# ST_LINK_V2-1.net
KiCad netlist of a schematic drawn in Altium Designer
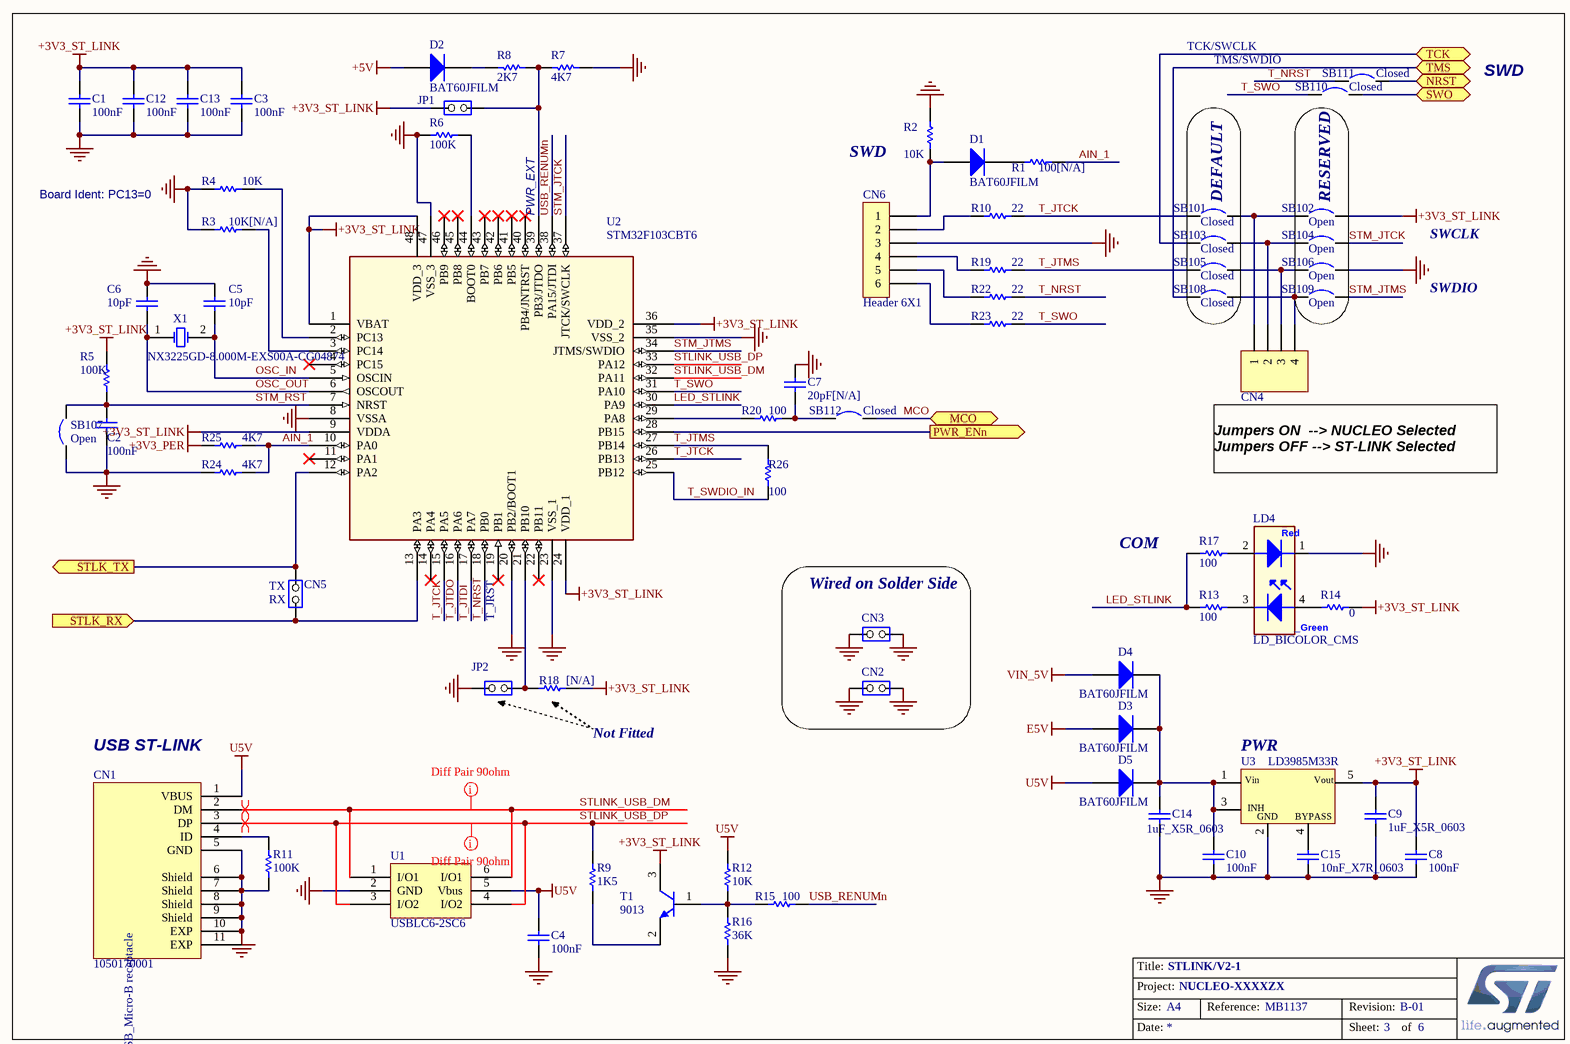
[diagram p0: ST_LINK_V2-1.SCHDOC]

(export (version "E")
  (design (tool "Eeschema 10.0.6"))
  (components
    (comp (ref "C1")
      (value "100nF")
      (footprint "0603C")
      (description "Capacitor 0402 / 0603 / 0805")
      (libsource (lib "MCD_TOOLS") (part "Capacitor_ST"))
    )
    (comp (ref "C2")
      (value "100nF")
      (footprint "0603C")
      (description "Capacitor 0402 / 0603 / 0805")
      (libsource (lib "MCD_TOOLS") (part "Capacitor_ST"))
    )
    (comp (ref "C3")
      (value "100nF")
      (footprint "0603C")
      (description "Capacitor 0402 / 0603 / 0805")
      (libsource (lib "MCD_TOOLS") (part "Capacitor_ST"))
    )
    (comp (ref "C4")
      (value "100nF")
      (footprint "0603C")
      (description "Capacitor 0402 / 0603 / 0805")
      (libsource (lib "MCD_TOOLS") (part "Capacitor_ST"))
    )
    (comp (ref "C5")
      (value "10pF")
      (footprint "0603C")
      (description "Capacitor 0402 / 0603 / 0805")
      (libsource (lib "MCD_TOOLS") (part "Capacitor_ST"))
    )
    (comp (ref "C6")
      (value "10pF")
      (footprint "0603C")
      (description "Capacitor 0402 / 0603 / 0805")
      (libsource (lib "MCD_TOOLS") (part "Capacitor_ST"))
    )
    (comp (ref "C7")
      (value "20pF[N/A]")
      (footprint "0603C")
      (description "Capacitor 0402 / 0603 / 0805")
      (libsource (lib "MCD_TOOLS") (part "Capacitor_ST"))
    )
    (comp (ref "C8")
      (value "100nF")
      (footprint "0603C")
      (description "Capacitor 0402 / 0603 / 0805")
      (libsource (lib "MCD_TOOLS") (part "Capacitor_ST"))
    )
    (comp (ref "C9")
      (value "1uF_X5R_0603")
      (footprint "0603C")
      (description "0603  X5R 1µF")
      (fields (field (name "TOLERANCE") "10%"))
      (libsource (lib "MB963_1") (part "CAP SMD 0603  X5R 1µF 25V 10%"))
    )
    (comp (ref "C10")
      (value "100nF")
      (footprint "0603C")
      (description "Capacitor 0402 / 0603 / 0805")
      (libsource (lib "MCD_TOOLS") (part "Capacitor_ST"))
    )
    (comp (ref "C12")
      (value "100nF")
      (footprint "0603C")
      (description "Capacitor 0402 / 0603 / 0805")
      (libsource (lib "MCD_TOOLS") (part "Capacitor_ST"))
    )
    (comp (ref "C13")
      (value "100nF")
      (footprint "0603C")
      (description "Capacitor 0402 / 0603 / 0805")
      (libsource (lib "MCD_TOOLS") (part "Capacitor_ST"))
    )
    (comp (ref "C14")
      (value "1uF_X5R_0603")
      (footprint "0603C")
      (description "0603  X5R 1µF")
      (fields (field (name "TOLERANCE") "10%"))
      (libsource (lib "MB963_1") (part "CAP SMD 0603  X5R 1µF 25V 10%"))
    )
    (comp (ref "C15")
      (value "10nF_X7R_0603")
      (footprint "0603C")
      (description "0603  X7R 10NF")
      (fields (field (name "TOLERANCE") "10%"))
      (libsource (lib "MB963_1") (part "CAP SMD 0603  X7R 10000PF 50V 10%"))
    )
    (comp (ref "CN1")
      (value "1050170001")
      (footprint "Molex_1050170001")
      (libsource (lib "Smartphone_accessory") (part "1050170001"))
    )
    (comp (ref "CN2") (value "~") (footprint "HDR_1x2_2R54_V_M") (libsource (lib "*") (part "JP2")))
    (comp (ref "CN3") (value "~") (footprint "HDR_1x2_2R54_V_M") (libsource (lib "*") (part "JP2")))
    (comp (ref "CN4")
      (value "Header 4")
      (footprint "HDR_1x4_2R54_V_M")
      (description "Header, 4-Pin, Single row")
      (fields (field (name "PUBLISHER") "Altium Limited"))
      (libsource (lib "Nucleo_64") (part "Header 4"))
    )
    (comp (ref "CN5") (value "~") (footprint "HDR_1x2_2R54_V_M_S") (libsource (lib "MCD_TOOLS") (part "JP2")))
    (comp (ref "CN6")
      (value "Header 6X1")
      (footprint "HDR_1x6_2R54_V_M")
      (description "Header, 6-Pin, Single row")
      (fields (field (name "PUBLISHER") "Altium Limited"))
      (libsource (lib "Nucleo_64") (part "Header 6X1"))
    )
    (comp (ref "D1")
      (value "BAT60JFILM")
      (footprint "SOD-323")
      (libsource (lib "MB1137") (part "BAT60JFILM"))
    )
    (comp (ref "D2")
      (value "BAT60JFILM")
      (footprint "SOD-323")
      (description "Default Diode")
      (fields (field (name "PUBLISHER") "Altium Limited"))
      (libsource (lib "MB1144_1") (part "Diode"))
    )
    (comp (ref "D3")
      (value "BAT60JFILM")
      (footprint "SOD-323")
      (libsource (lib "MB1137") (part "BAT60JFILM"))
    )
    (comp (ref "D4")
      (value "BAT60JFILM")
      (footprint "SOD-323")
      (libsource (lib "MB1137") (part "BAT60JFILM"))
    )
    (comp (ref "D5")
      (value "BAT60JFILM")
      (footprint "SOD-323")
      (libsource (lib "MB1137") (part "BAT60JFILM"))
    )
    (comp (ref "JP1") (value "~") (footprint "HDR_1x2_2R54_V_M_S") (libsource (lib "*") (part "JP2")))
    (comp (ref "JP2") (value "~") (footprint "HDR_1x2_2R54_V_M_S") (libsource (lib "*") (part "JP2")))
    (comp (ref "LD4")
      (value "LD_BICOLOR_CMS")
      (footprint "HSMF-A201")
      (description "Bicolor Led")
      (libsource (lib "MB1137") (part "LD_BICOLOR_CMS"))
    )
    (comp (ref "R1")
      (value "100[N/A]")
      (footprint "0603R")
      (description "Resistor 0402 / 0603 / 0805")
      (libsource (lib "Miscellaneous Devices") (part "Res1"))
    )
    (comp (ref "R2")
      (value "10K")
      (footprint "0603R")
      (description "Resistor 0402 / 0603 / 0805")
      (libsource (lib "Miscellaneous Devices") (part "Res1"))
    )
    (comp (ref "R3")
      (value "10K[N/A]")
      (footprint "0603R")
      (description "Resistor 0402 / 0603 / 0805")
      (libsource (lib "Miscellaneous Devices") (part "Res1"))
    )
    (comp (ref "R4")
      (value "10K")
      (footprint "0603R")
      (description "Resistor 0402 / 0603 / 0805")
      (libsource (lib "Miscellaneous Devices") (part "Res1"))
    )
    (comp (ref "R5")
      (value "100K")
      (footprint "0603R")
      (description "Resistor 0402 / 0603 / 0805")
      (libsource (lib "Miscellaneous Devices") (part "Res1"))
    )
    (comp (ref "R6")
      (value "100K")
      (footprint "0603R")
      (description "Resistor 0402 / 0603 / 0805")
      (libsource (lib "Miscellaneous Devices") (part "Res1"))
    )
    (comp (ref "R7")
      (value "4K7")
      (footprint "0603R")
      (description "Resistor")
      (fields (field (name "PUBLISHER") "Altium Limited"))
      (libsource (lib "") (part "Res1_2"))
    )
    (comp (ref "R8")
      (value "2K7")
      (footprint "0603R")
      (description "Resistor")
      (fields (field (name "PUBLISHER") "Altium Limited"))
      (libsource (lib "") (part "Res1_2"))
    )
    (comp (ref "R9")
      (value "1K5")
      (footprint "0603R")
      (description "Resistor 0402 / 0603 / 0805")
      (libsource (lib "Miscellaneous Devices") (part "Res1"))
    )
    (comp (ref "R10")
      (value "22")
      (footprint "0603R")
      (description "Resistor 0402 / 0603 / 0805")
      (libsource (lib "Miscellaneous Devices") (part "Res1"))
    )
    (comp (ref "R11")
      (value "100K")
      (footprint "0603R")
      (description "Resistor 0402 / 0603 / 0805")
      (libsource (lib "Miscellaneous Devices") (part "Res1"))
    )
    (comp (ref "R12")
      (value "10K")
      (footprint "0603R")
      (description "Resistor")
      (fields (field (name "PUBLISHER") "Altium Limited"))
      (libsource (lib "") (part "Res1_1"))
    )
    (comp (ref "R13")
      (value "100")
      (footprint "0603R")
      (description "Resistor 0402 / 0603 / 0805")
      (libsource (lib "Miscellaneous Devices") (part "Res1"))
    )
    (comp (ref "R14")
      (value "0")
      (footprint "0603R")
      (description "Resistor 0402 / 0603 / 0805")
      (libsource (lib "Miscellaneous Devices") (part "Res1"))
    )
    (comp (ref "R15")
      (value "100")
      (footprint "0603R")
      (description "Resistor 0402 / 0603 / 0805")
      (libsource (lib "Miscellaneous Devices") (part "Res1"))
    )
    (comp (ref "R16")
      (value "36K")
      (footprint "0603R")
      (description "Resistor")
      (fields (field (name "PUBLISHER") "Altium Limited"))
      (libsource (lib "") (part "Res1_1"))
    )
    (comp (ref "R17")
      (value "100")
      (footprint "0603R")
      (description "Resistor 0402 / 0603 / 0805")
      (libsource (lib "Miscellaneous Devices") (part "Res1"))
    )
    (comp (ref "R18")
      (value "[N/A]")
      (footprint "0603R")
      (description "Resistor")
      (fields (field (name "PUBLISHER") "Altium Limited"))
      (libsource (lib "") (part "Res1_1"))
    )
    (comp (ref "R19")
      (value "22")
      (footprint "0603R")
      (description "Resistor 0402 / 0603 / 0805")
      (libsource (lib "Miscellaneous Devices") (part "Res1"))
    )
    (comp (ref "R20")
      (value "100")
      (footprint "0603R")
      (description "Resistor 0402 / 0603 / 0805")
      (libsource (lib "Miscellaneous Devices") (part "Res1"))
    )
    (comp (ref "R22")
      (value "22")
      (footprint "0603R")
      (description "Resistor 0402 / 0603 / 0805")
      (libsource (lib "Miscellaneous Devices") (part "Res1"))
    )
    (comp (ref "R23")
      (value "22")
      (footprint "0603R")
      (description "Resistor 0402 / 0603 / 0805")
      (libsource (lib "Miscellaneous Devices") (part "Res1"))
    )
    (comp (ref "R24")
      (value "4K7")
      (footprint "0603R")
      (description "Resistor 0402 / 0603 / 0805")
      (libsource (lib "Miscellaneous Devices") (part "Res1"))
    )
    (comp (ref "R25")
      (value "4K7")
      (footprint "0603R")
      (description "Resistor 0402 / 0603 / 0805")
      (libsource (lib "Miscellaneous Devices") (part "Res1"))
    )
    (comp (ref "R26")
      (value "100")
      (footprint "0603R")
      (description "Resistor 0402 / 0603 / 0805")
      (libsource (lib "Miscellaneous Devices") (part "Res1"))
    )
    (comp (ref "SB101")
      (value "Closed")
      (footprint "SB_0603")
      (description "Circuit Breaker")
      (fields (field (name "PUBLISHER") "Altium Limited"))
      (libsource (lib "MB1167") (part "Circuit Breaker_close"))
    )
    (comp (ref "SB102")
      (value "Open")
      (footprint "SB_0603")
      (description "Circuit Breaker")
      (fields (field (name "PUBLISHER") "Altium Limited"))
      (libsource (lib "MB1167") (part "Circuit Breaker"))
    )
    (comp (ref "SB103")
      (value "Closed")
      (footprint "SB_0603")
      (description "Circuit Breaker")
      (fields (field (name "PUBLISHER") "Altium Limited"))
      (libsource (lib "MB1167") (part "Circuit Breaker_close"))
    )
    (comp (ref "SB104")
      (value "Open")
      (footprint "SB_0603")
      (description "Circuit Breaker")
      (fields (field (name "PUBLISHER") "Altium Limited"))
      (libsource (lib "MB1167") (part "Circuit Breaker"))
    )
    (comp (ref "SB105")
      (value "Closed")
      (footprint "SB_0603")
      (description "Circuit Breaker")
      (fields (field (name "PUBLISHER") "Altium Limited"))
      (libsource (lib "MB1167") (part "Circuit Breaker_close"))
    )
    (comp (ref "SB106")
      (value "Open")
      (footprint "SB_0603")
      (description "Circuit Breaker")
      (fields (field (name "PUBLISHER") "Altium Limited"))
      (libsource (lib "MB1167") (part "Circuit Breaker"))
    )
    (comp (ref "SB107")
      (value "Open")
      (footprint "SB_0603")
      (description "Circuit Breaker")
      (fields (field (name "PUBLISHER") "Altium Limited"))
      (libsource (lib "MB1167") (part "Circuit Breaker"))
    )
    (comp (ref "SB108")
      (value "Closed")
      (footprint "SB_0603")
      (description "Circuit Breaker")
      (fields (field (name "PUBLISHER") "Altium Limited"))
      (libsource (lib "MB1167") (part "Circuit Breaker_close"))
    )
    (comp (ref "SB109")
      (value "Open")
      (footprint "SB_0603")
      (description "Circuit Breaker")
      (fields (field (name "PUBLISHER") "Altium Limited"))
      (libsource (lib "MB1167") (part "Circuit Breaker"))
    )
    (comp (ref "SB110")
      (value "Closed")
      (footprint "SB_0603")
      (description "Circuit Breaker")
      (fields (field (name "PUBLISHER") "Altium Limited"))
      (libsource (lib "MB1167") (part "Circuit Breaker_close"))
    )
    (comp (ref "SB111")
      (value "Closed")
      (footprint "SB_0603")
      (description "Circuit Breaker")
      (fields (field (name "PUBLISHER") "Altium Limited"))
      (libsource (lib "MB1167") (part "Circuit Breaker_close"))
    )
    (comp (ref "SB112")
      (value "Closed")
      (footprint "SB_0603")
      (description "Circuit Breaker")
      (fields (field (name "PUBLISHER") "Altium Limited"))
      (libsource (lib "MB1167") (part "Circuit Breaker_close"))
    )
    (comp (ref "T1")
      (value "9013")
      (footprint "SOT-23")
      (description "NPN Bipolar Transistor")
      (fields (field (name "PUBLISHER") "Altium Limited"))
      (libsource (lib "MB1167") (part "NPN"))
    )
    (comp (ref "U1")
      (value "USBLC6-2SC6")
      (footprint "SOT23-6L")
      (libsource (lib "MB1137") (part "USBLC6-2SC6"))
    )
    (comp (ref "U2")
      (value "STM32F103CBT6")
      (footprint "LQFP48_0R5_7x7")
      (description "Medium-density performance line ARM-based 32-bit MCU with 64KB Flash")
      (libsource (lib "Nucleo_64") (part "STM32F103CBT6"))
    )
    (comp (ref "U3")
      (value "LD3985M33R")
      (footprint "SOT-23-5L")
      (description "Ultra low drop-low noise BiCMOS voltage, regulators low ESR capacitors compatible")
      (libsource (lib "MCD_TOOLS") (part "LD3985M33R"))
    )
    (comp (ref "X1")
      (value "NX3225GD-8.000M-EXS00A-CG04874")
      (footprint "OSC_2SM_3R2x2R5")
      (description "Crystal Oscillator")
      (fields (field (name "PUBLISHER") "Altium Limited"))
      (libsource (lib "MB963_1") (part "XTAL"))
    )
  )
  (nets
    (net (code "1") (name "+3V3_PER") (class "Default")
      (node (ref "R25") (pin "1") (pinfunction "1_1") (pintype "passive"))
    )
    (net (code "2") (name "+3V3_ST_LINK") (class "Default")
      (node (ref "C1") (pin "2") (pinfunction "2_2") (pintype "passive"))
      (node (ref "C12") (pin "2") (pinfunction "2_2") (pintype "passive"))
      (node (ref "C13") (pin "2") (pinfunction "2_2") (pintype "passive"))
      (node (ref "C3") (pin "2") (pinfunction "2_2") (pintype "passive"))
      (node (ref "C8") (pin "2") (pinfunction "2_2") (pintype "passive"))
      (node (ref "C9") (pin "1") (pinfunction "1_1") (pintype "passive"))
      (node (ref "JP1") (pin "1") (pinfunction "COMMON_1") (pintype "passive"))
      (node (ref "R14") (pin "2") (pinfunction "2_2") (pintype "passive"))
      (node (ref "R18") (pin "1") (pinfunction "1_1") (pintype "passive"))
      (node (ref "R5") (pin "2") (pinfunction "2_2") (pintype "passive"))
      (node (ref "SB102") (pin "2") (pinfunction "2_2") (pintype "passive"))
      (node (ref "T1") (pin "3") (pinfunction "C_3") (pintype "passive"))
      (node (ref "U2") (pin "1") (pinfunction "VBAT_1") (pintype "power_in"))
      (node (ref "U2") (pin "24") (pinfunction "VDD_1_24") (pintype "power_in"))
      (node (ref "U2") (pin "36") (pinfunction "VDD_2_36") (pintype "power_in"))
      (node (ref "U2") (pin "48") (pinfunction "VDD_3_48") (pintype "power_in"))
      (node (ref "U2") (pin "9") (pinfunction "VDDA_9") (pintype "power_in"))
      (node (ref "U3") (pin "5") (pinfunction "Vout_5") (pintype "passive"))
    )
    (net (code "3") (name "+5V") (class "Default")
      (node (ref "D2") (pin "1") (pinfunction "A_1") (pintype "passive"))
    )
    (net (code "4") (name "/AIN_1") (class "Default")
      (node (ref "R1") (pin "2") (pinfunction "2_2") (pintype "passive"))
      (node (ref "R24") (pin "2") (pinfunction "2_2") (pintype "passive"))
      (node (ref "R25") (pin "2") (pinfunction "2_2") (pintype "passive"))
      (node (ref "U2") (pin "10") (pinfunction "PA0_10") (pintype "bidirectional"))
    )
    (net (code "5") (name "/LED_STLINK") (class "Default")
      (node (ref "R13") (pin "1") (pinfunction "1_1") (pintype "passive"))
      (node (ref "R17") (pin "1") (pinfunction "1_1") (pintype "passive"))
      (node (ref "U2") (pin "30") (pinfunction "PA9_30") (pintype "bidirectional"))
    )
    (net (code "6") (name "/MCO") (class "Default")
      (node (ref "SB112") (pin "2") (pinfunction "2_2") (pintype "passive"))
    )
    (net (code "7") (name "/NRST") (class "Default")
      (node (ref "SB111") (pin "2") (pinfunction "2_2") (pintype "passive"))
    )
    (net (code "8") (name "/OSC_IN") (class "Default")
      (node (ref "C5") (pin "1") (pinfunction "1_1") (pintype "passive"))
      (node (ref "U2") (pin "5") (pinfunction "OSCIN_5") (pintype "input"))
      (node (ref "X1") (pin "2") (pinfunction "OSC2_2") (pintype "passive"))
    )
    (net (code "9") (name "/OSC_OUT") (class "Default")
      (node (ref "C6") (pin "1") (pinfunction "1_1") (pintype "passive"))
      (node (ref "U2") (pin "6") (pinfunction "OSCOUT_6") (pintype "output"))
      (node (ref "X1") (pin "1") (pinfunction "OSC1_1") (pintype "passive"))
    )
    (net (code "10") (name "/PWR_ENn") (class "Default")
      (node (ref "U2") (pin "28") (pinfunction "PB15_28") (pintype "bidirectional"))
    )
    (net (code "11") (name "/STLINK_USB_DM") (class "Default")
      (node (ref "CN1") (pin "2") (pinfunction "DM_2") (pintype "passive"))
      (node (ref "U1") (pin "1") (pinfunction "I/O1_1") (pintype "passive"))
      (node (ref "U1") (pin "6") (pinfunction "I/O1_6") (pintype "passive"))
      (node (ref "U2") (pin "32") (pinfunction "PA11_32") (pintype "bidirectional"))
    )
    (net (code "12") (name "/STLINK_USB_DP") (class "Default")
      (node (ref "CN1") (pin "3") (pinfunction "DP_3") (pintype "passive"))
      (node (ref "R9") (pin "1") (pinfunction "1_1") (pintype "passive"))
      (node (ref "U1") (pin "3") (pinfunction "I/O2_3") (pintype "passive"))
      (node (ref "U1") (pin "4") (pinfunction "I/O2_4") (pintype "passive"))
      (node (ref "U2") (pin "33") (pinfunction "PA12_33") (pintype "bidirectional"))
    )
    (net (code "13") (name "/STLK_RX") (class "Default")
      (node (ref "CN5") (pin "1") (pinfunction "COMMON_1") (pintype "passive"))
      (node (ref "U2") (pin "13") (pinfunction "PA3_13") (pintype "bidirectional"))
    )
    (net (code "14") (name "/STLK_TX") (class "Default")
      (node (ref "CN5") (pin "2") (pinfunction "NO_2") (pintype "passive"))
      (node (ref "U2") (pin "12") (pinfunction "PA2_12") (pintype "bidirectional"))
    )
    (net (code "15") (name "/STM_JTCK") (class "Default")
      (node (ref "SB104") (pin "2") (pinfunction "2_2") (pintype "passive"))
      (node (ref "U2") (pin "37") (pinfunction "JTCK/SWCLK_37") (pintype "bidirectional"))
    )
    (net (code "16") (name "/STM_JTMS") (class "Default")
      (node (ref "SB109") (pin "2") (pinfunction "2_2") (pintype "passive"))
      (node (ref "U2") (pin "34") (pinfunction "JTMS/SWDIO_34") (pintype "bidirectional"))
    )
    (net (code "17") (name "/STM_RST") (class "Default")
      (node (ref "C2") (pin "2") (pinfunction "2_2") (pintype "passive"))
      (node (ref "R5") (pin "1") (pinfunction "1_1") (pintype "passive"))
      (node (ref "SB107") (pin "2") (pinfunction "2_2") (pintype "passive"))
      (node (ref "U2") (pin "7") (pinfunction "NRST_7") (pintype "input"))
    )
    (net (code "18") (name "/SWO") (class "Default")
      (node (ref "SB110") (pin "2") (pinfunction "2_2") (pintype "passive"))
    )
    (net (code "19") (name "/TCK") (class "Default")
      (node (ref "SB103") (pin "1") (pinfunction "1_1") (pintype "passive"))
    )
    (net (code "20") (name "/TMS") (class "Default")
      (node (ref "SB108") (pin "1") (pinfunction "1_1") (pintype "passive"))
    )
    (net (code "21") (name "/T_JTCK") (class "Default")
      (node (ref "R10") (pin "2") (pinfunction "2_2") (pintype "passive"))
      (node (ref "SB101") (pin "1") (pinfunction "1_1") (pintype "passive"))
      (node (ref "U2") (pin "15") (pinfunction "PA5_15") (pintype "bidirectional"))
      (node (ref "U2") (pin "26") (pinfunction "PB13_26") (pintype "bidirectional"))
    )
    (net (code "22") (name "/T_JTDI") (class "Default")
      (node (ref "U2") (pin "17") (pinfunction "PA7_17") (pintype "bidirectional"))
    )
    (net (code "23") (name "/T_JTDO") (class "Default")
      (node (ref "U2") (pin "16") (pinfunction "PA6_16") (pintype "bidirectional"))
    )
    (net (code "24") (name "/T_JTMS") (class "Default")
      (node (ref "R19") (pin "2") (pinfunction "2_2") (pintype "passive"))
      (node (ref "R26") (pin "2") (pinfunction "2_2") (pintype "passive"))
      (node (ref "SB105") (pin "1") (pinfunction "1_1") (pintype "passive"))
      (node (ref "U2") (pin "27") (pinfunction "PB14_27") (pintype "bidirectional"))
    )
    (net (code "25") (name "/T_NRST") (class "Default")
      (node (ref "R22") (pin "2") (pinfunction "2_2") (pintype "passive"))
      (node (ref "SB111") (pin "1") (pinfunction "1_1") (pintype "passive"))
      (node (ref "U2") (pin "18") (pinfunction "PB0_18") (pintype "bidirectional"))
    )
    (net (code "26") (name "/T_SWDIO_IN") (class "Default")
      (node (ref "R26") (pin "1") (pinfunction "1_1") (pintype "passive"))
      (node (ref "U2") (pin "25") (pinfunction "PB12_25") (pintype "bidirectional"))
    )
    (net (code "27") (name "/T_SWO") (class "Default")
      (node (ref "R23") (pin "2") (pinfunction "2_2") (pintype "passive"))
      (node (ref "SB110") (pin "1") (pinfunction "1_1") (pintype "passive"))
      (node (ref "U2") (pin "31") (pinfunction "PA10_31") (pintype "bidirectional"))
    )
    (net (code "28") (name "/USB_RENUMn") (class "Default")
      (node (ref "R15") (pin "2") (pinfunction "2_2") (pintype "passive"))
      (node (ref "U2") (pin "38") (pinfunction "PA15/JTDI_38") (pintype "bidirectional"))
    )
    (net (code "29") (name "E5V") (class "Default")
      (node (ref "D3") (pin "1") (pinfunction "A_1") (pintype "passive"))
    )
    (net (code "30") (name "GND") (class "Default")
      (node (ref "C1") (pin "1") (pinfunction "1_1") (pintype "passive"))
      (node (ref "C10") (pin "1") (pinfunction "1_1") (pintype "passive"))
      (node (ref "C12") (pin "1") (pinfunction "1_1") (pintype "passive"))
      (node (ref "C13") (pin "1") (pinfunction "1_1") (pintype "passive"))
      (node (ref "C14") (pin "1") (pinfunction "1_1") (pintype "passive"))
      (node (ref "C15") (pin "1") (pinfunction "1_1") (pintype "passive"))
      (node (ref "C2") (pin "1") (pinfunction "1_1") (pintype "passive"))
      (node (ref "C3") (pin "1") (pinfunction "1_1") (pintype "passive"))
      (node (ref "C4") (pin "1") (pinfunction "1_1") (pintype "passive"))
      (node (ref "C5") (pin "2") (pinfunction "2_2") (pintype "passive"))
      (node (ref "C6") (pin "2") (pinfunction "2_2") (pintype "passive"))
      (node (ref "C7") (pin "2") (pinfunction "2_2") (pintype "passive"))
      (node (ref "C8") (pin "1") (pinfunction "1_1") (pintype "passive"))
      (node (ref "C9") (pin "2") (pinfunction "2_2") (pintype "passive"))
      (node (ref "CN1") (pin "10") (pinfunction "EXP_10") (pintype "passive"))
      (node (ref "CN1") (pin "5") (pinfunction "GND_5") (pintype "passive"))
      (node (ref "CN1") (pin "6") (pinfunction "Shield_6") (pintype "passive"))
      (node (ref "CN1") (pin "7") (pinfunction "Shield_7") (pintype "passive"))
      (node (ref "CN1") (pin "8") (pinfunction "Shield_8") (pintype "passive"))
      (node (ref "CN1") (pin "9") (pinfunction "Shield_9") (pintype "passive"))
      (node (ref "CN2") (pin "1") (pinfunction "COMMON_1") (pintype "passive"))
      (node (ref "CN2") (pin "2") (pinfunction "NO_2") (pintype "passive"))
      (node (ref "CN3") (pin "1") (pinfunction "COMMON_1") (pintype "passive"))
      (node (ref "CN3") (pin "2") (pinfunction "NO_2") (pintype "passive"))
      (node (ref "CN6") (pin "3") (pinfunction "3_3") (pintype "passive"))
      (node (ref "JP2") (pin "1") (pinfunction "COMMON_1") (pintype "passive"))
      (node (ref "LD4") (pin "1") (pinfunction "1_1") (pintype "passive"))
      (node (ref "R11") (pin "2") (pinfunction "2_2") (pintype "passive"))
      (node (ref "R16") (pin "1") (pinfunction "1_1") (pintype "passive"))
      (node (ref "R2") (pin "2") (pinfunction "2_2") (pintype "passive"))
      (node (ref "R24") (pin "1") (pinfunction "1_1") (pintype "passive"))
      (node (ref "R3") (pin "1") (pinfunction "1_1") (pintype "passive"))
      (node (ref "R4") (pin "1") (pinfunction "1_1") (pintype "passive"))
      (node (ref "R6") (pin "1") (pinfunction "1_1") (pintype "passive"))
      (node (ref "R7") (pin "2") (pinfunction "2_2") (pintype "passive"))
      (node (ref "SB106") (pin "2") (pinfunction "2_2") (pintype "passive"))
      (node (ref "SB107") (pin "1") (pinfunction "1_1") (pintype "passive"))
      (node (ref "U1") (pin "2") (pinfunction "GND_2") (pintype "passive"))
      (node (ref "U2") (pin "20") (pinfunction "PB2/BOOT1_20") (pintype "bidirectional"))
      (node (ref "U2") (pin "23") (pinfunction "VSS_1_23") (pintype "power_in"))
      (node (ref "U2") (pin "35") (pinfunction "VSS_2_35") (pintype "power_in"))
      (node (ref "U2") (pin "47") (pinfunction "VSS_3_47") (pintype "power_in"))
      (node (ref "U2") (pin "8") (pinfunction "VSSA_8") (pintype "power_in"))
      (node (ref "U3") (pin "2") (pinfunction "GND_2") (pintype "passive"))
    )
    (net (code "31") (name "Net-(C7-Pad1)") (class "Default")
      (node (ref "C7") (pin "1") (pinfunction "1_1") (pintype "passive"))
      (node (ref "R20") (pin "2") (pinfunction "2_2") (pintype "passive"))
      (node (ref "SB112") (pin "1") (pinfunction "1_1") (pintype "passive"))
    )
    (net (code "32") (name "Net-(CN1-ID)") (class "Default")
      (node (ref "CN1") (pin "4") (pinfunction "ID_4") (pintype "passive"))
      (node (ref "R11") (pin "1") (pinfunction "1_1") (pintype "passive"))
    )
    (net (code "33") (name "Net-(CN4-Pad1)") (class "Default")
      (node (ref "CN4") (pin "1") (pinfunction "1_1") (pintype "passive"))
      (node (ref "SB101") (pin "2") (pinfunction "2_2") (pintype "passive"))
      (node (ref "SB102") (pin "1") (pinfunction "1_1") (pintype "passive"))
    )
    (net (code "34") (name "Net-(CN4-Pad2)") (class "Default")
      (node (ref "CN4") (pin "2") (pinfunction "2_2") (pintype "passive"))
      (node (ref "SB103") (pin "2") (pinfunction "2_2") (pintype "passive"))
      (node (ref "SB104") (pin "1") (pinfunction "1_1") (pintype "passive"))
    )
    (net (code "35") (name "Net-(CN4-Pad3)") (class "Default")
      (node (ref "CN4") (pin "3") (pinfunction "3_3") (pintype "passive"))
      (node (ref "SB105") (pin "2") (pinfunction "2_2") (pintype "passive"))
      (node (ref "SB106") (pin "1") (pinfunction "1_1") (pintype "passive"))
    )
    (net (code "36") (name "Net-(CN4-Pad4)") (class "Default")
      (node (ref "CN4") (pin "4") (pinfunction "4_4") (pintype "passive"))
      (node (ref "SB108") (pin "2") (pinfunction "2_2") (pintype "passive"))
      (node (ref "SB109") (pin "1") (pinfunction "1_1") (pintype "passive"))
    )
    (net (code "37") (name "Net-(CN6-Pad2)") (class "Default")
      (node (ref "CN6") (pin "2") (pinfunction "2_2") (pintype "passive"))
      (node (ref "R10") (pin "1") (pinfunction "1_1") (pintype "passive"))
    )
    (net (code "38") (name "Net-(CN6-Pad4)") (class "Default")
      (node (ref "CN6") (pin "4") (pinfunction "4_4") (pintype "passive"))
      (node (ref "R19") (pin "1") (pinfunction "1_1") (pintype "passive"))
    )
    (net (code "39") (name "Net-(CN6-Pad5)") (class "Default")
      (node (ref "CN6") (pin "5") (pinfunction "5_5") (pintype "passive"))
      (node (ref "R22") (pin "1") (pinfunction "1_1") (pintype "passive"))
    )
    (net (code "40") (name "Net-(CN6-Pad6)") (class "Default")
      (node (ref "CN6") (pin "6") (pinfunction "6_6") (pintype "passive"))
      (node (ref "R23") (pin "1") (pinfunction "1_1") (pintype "passive"))
    )
    (net (code "41") (name "Net-(D1-A)") (class "Default")
      (node (ref "CN6") (pin "1") (pinfunction "1_1") (pintype "passive"))
      (node (ref "D1") (pin "1") (pinfunction "A_1") (pintype "passive"))
      (node (ref "R2") (pin "1") (pinfunction "1_1") (pintype "passive"))
    )
    (net (code "42") (name "Net-(D1-K)") (class "Default")
      (node (ref "D1") (pin "2") (pinfunction "K_2") (pintype "passive"))
      (node (ref "R1") (pin "1") (pinfunction "1_1") (pintype "passive"))
    )
    (net (code "43") (name "Net-(D2-K)") (class "Default")
      (node (ref "D2") (pin "2") (pinfunction "K_2") (pintype "passive"))
      (node (ref "R8") (pin "1") (pinfunction "1_1") (pintype "passive"))
    )
    (net (code "44") (name "Net-(D3-K)") (class "Default")
      (node (ref "C10") (pin "2") (pinfunction "2_2") (pintype "passive"))
      (node (ref "C14") (pin "2") (pinfunction "2_2") (pintype "passive"))
      (node (ref "D3") (pin "2") (pinfunction "K_2") (pintype "passive"))
      (node (ref "D4") (pin "2") (pinfunction "K_2") (pintype "passive"))
      (node (ref "D5") (pin "2") (pinfunction "K_2") (pintype "passive"))
      (node (ref "U3") (pin "1") (pinfunction "Vin_1") (pintype "passive"))
      (node (ref "U3") (pin "3") (pinfunction "CE_3") (pintype "passive"))
    )
    (net (code "45") (name "Net-(JP1-NO)") (class "Default")
      (node (ref "JP1") (pin "2") (pinfunction "NO_2") (pintype "passive"))
      (node (ref "R7") (pin "1") (pinfunction "1_1") (pintype "passive"))
      (node (ref "R8") (pin "2") (pinfunction "2_2") (pintype "passive"))
      (node (ref "U2") (pin "39") (pinfunction "PB3/JTDO_39") (pintype "bidirectional"))
    )
    (net (code "46") (name "Net-(JP2-NO)") (class "Default")
      (node (ref "JP2") (pin "2") (pinfunction "NO_2") (pintype "passive"))
      (node (ref "R18") (pin "2") (pinfunction "2_2") (pintype "passive"))
      (node (ref "U2") (pin "21") (pinfunction "PB10_21") (pintype "bidirectional"))
    )
    (net (code "47") (name "Net-(LD4-Pad2)") (class "Default")
      (node (ref "LD4") (pin "2") (pinfunction "2_2") (pintype "passive"))
      (node (ref "R17") (pin "2") (pinfunction "2_2") (pintype "passive"))
    )
    (net (code "48") (name "Net-(LD4-Pad3)") (class "Default")
      (node (ref "LD4") (pin "3") (pinfunction "3_3") (pintype "passive"))
      (node (ref "R13") (pin "2") (pinfunction "2_2") (pintype "passive"))
    )
    (net (code "49") (name "Net-(LD4-Pad4)") (class "Default")
      (node (ref "LD4") (pin "4") (pinfunction "4_4") (pintype "passive"))
      (node (ref "R14") (pin "1") (pinfunction "1_1") (pintype "passive"))
    )
    (net (code "50") (name "Net-(T1-B)") (class "Default")
      (node (ref "R12") (pin "1") (pinfunction "1_1") (pintype "passive"))
      (node (ref "R15") (pin "1") (pinfunction "1_1") (pintype "passive"))
      (node (ref "R16") (pin "2") (pinfunction "2_2") (pintype "passive"))
      (node (ref "T1") (pin "1") (pinfunction "B_1") (pintype "passive"))
    )
    (net (code "51") (name "Net-(T1-E)") (class "Default")
      (node (ref "R9") (pin "2") (pinfunction "2_2") (pintype "passive"))
      (node (ref "T1") (pin "2") (pinfunction "E_2") (pintype "passive"))
    )
    (net (code "52") (name "Net-(U2-BOOT0)") (class "Default")
      (node (ref "R6") (pin "2") (pinfunction "2_2") (pintype "passive"))
      (node (ref "U2") (pin "44") (pinfunction "BOOT0_44") (pintype "bidirectional"))
    )
    (net (code "53") (name "Net-(U2-PA8)") (class "Default")
      (node (ref "R20") (pin "1") (pinfunction "1_1") (pintype "passive"))
      (node (ref "U2") (pin "29") (pinfunction "PA8_29") (pintype "bidirectional"))
    )
    (net (code "54") (name "Net-(U2-PC13)") (class "Default")
      (node (ref "R4") (pin "2") (pinfunction "2_2") (pintype "passive"))
      (node (ref "U2") (pin "2") (pinfunction "PC13_2") (pintype "bidirectional"))
    )
    (net (code "55") (name "Net-(U2-PC14)") (class "Default")
      (node (ref "R3") (pin "2") (pinfunction "2_2") (pintype "passive"))
      (node (ref "U2") (pin "3") (pinfunction "PC14_3") (pintype "bidirectional"))
    )
    (net (code "56") (name "Net-(U3-BYPASS)") (class "Default")
      (node (ref "C15") (pin "2") (pinfunction "2_2") (pintype "passive"))
      (node (ref "U3") (pin "4") (pinfunction "BYPASS_4") (pintype "passive"))
    )
    (net (code "57") (name "U5V") (class "Default")
      (node (ref "C4") (pin "2") (pinfunction "2_2") (pintype "passive"))
      (node (ref "CN1") (pin "1") (pinfunction "VBUS_1") (pintype "passive"))
      (node (ref "D5") (pin "1") (pinfunction "A_1") (pintype "passive"))
      (node (ref "R12") (pin "2") (pinfunction "2_2") (pintype "passive"))
      (node (ref "U1") (pin "5") (pinfunction "Vbus_5") (pintype "passive"))
    )
    (net (code "58") (name "VIN_5V") (class "Default")
      (node (ref "D4") (pin "1") (pinfunction "A_1") (pintype "passive"))
    )
    (net (code "59") (name "unconnected-(CN1-EXP-Pad11)") (class "Default")
      (node (ref "CN1") (pin "11") (pinfunction "EXP_11") (pintype "passive"))
    )
    (net (code "60") (name "unconnected-(U2-PA1-Pad11)") (class "Default")
      (node (ref "U2") (pin "11") (pinfunction "PA1_11") (pintype "bidirectional+no_connect"))
    )
    (net (code "61") (name "unconnected-(U2-PA4-Pad14)") (class "Default")
      (node (ref "U2") (pin "14") (pinfunction "PA4_14") (pintype "bidirectional+no_connect"))
    )
    (net (code "62") (name "unconnected-(U2-PB1-Pad19)") (class "Default")
      (node (ref "U2") (pin "19") (pinfunction "PB1_19") (pintype "input+no_connect"))
    )
    (net (code "63") (name "unconnected-(U2-PB4{slash}JNTRST-Pad40)") (class "Default")
      (node (ref "U2") (pin "40") (pinfunction "PB4/JNTRST_40") (pintype "bidirectional+no_connect"))
    )
    (net (code "64") (name "unconnected-(U2-PB5-Pad41)") (class "Default")
      (node (ref "U2") (pin "41") (pinfunction "PB5_41") (pintype "bidirectional+no_connect"))
    )
    (net (code "65") (name "unconnected-(U2-PB6-Pad42)") (class "Default")
      (node (ref "U2") (pin "42") (pinfunction "PB6_42") (pintype "bidirectional+no_connect"))
    )
    (net (code "66") (name "unconnected-(U2-PB7-Pad43)") (class "Default")
      (node (ref "U2") (pin "43") (pinfunction "PB7_43") (pintype "bidirectional+no_connect"))
    )
    (net (code "67") (name "unconnected-(U2-PB8-Pad45)") (class "Default")
      (node (ref "U2") (pin "45") (pinfunction "PB8_45") (pintype "bidirectional+no_connect"))
    )
    (net (code "68") (name "unconnected-(U2-PB9-Pad46)") (class "Default")
      (node (ref "U2") (pin "46") (pinfunction "PB9_46") (pintype "bidirectional+no_connect"))
    )
    (net (code "69") (name "unconnected-(U2-PB11-Pad22)") (class "Default")
      (node (ref "U2") (pin "22") (pinfunction "PB11_22") (pintype "bidirectional+no_connect"))
    )
    (net (code "70") (name "unconnected-(U2-PC15-Pad4)") (class "Default")
      (node (ref "U2") (pin "4") (pinfunction "PC15_4") (pintype "bidirectional+no_connect"))
    )
  )
)
